# test1.net
KiCad netlist of a schematic drawn in EAGLE
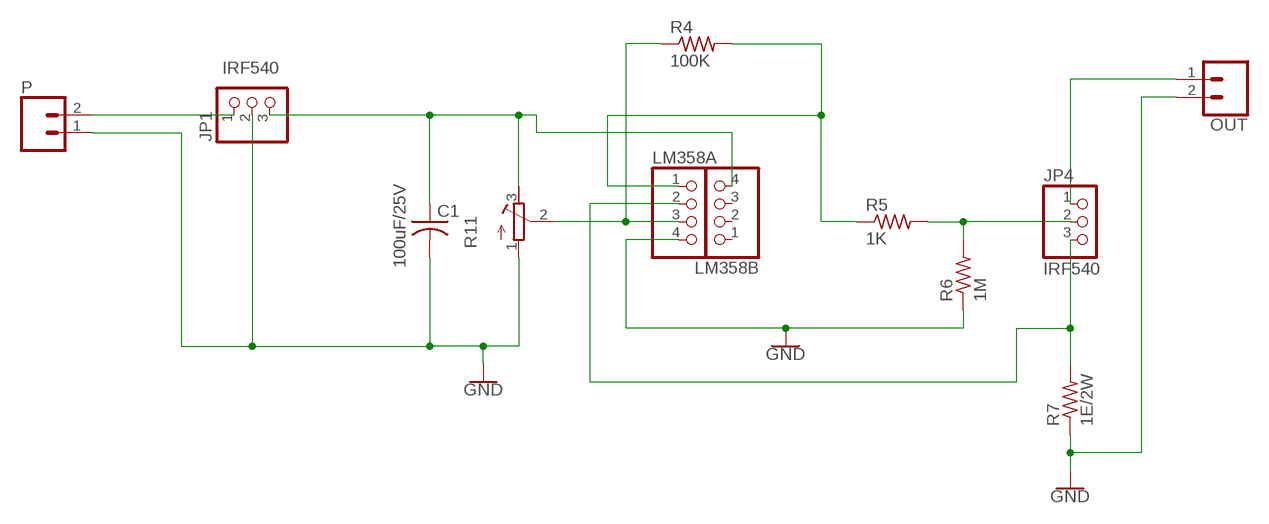
[diagram p0: schematic, sheet 1]

(export (version "E")
  (design (tool "Eeschema 10.0.6"))
  (components
    (comp (ref "C1")
      (value "100uF/25V")
      (footprint "eagle-import:C025-024X044")
      (libsource (lib "eagle-import") (part "C-US025-024X044"))
    )
    (comp (ref "JP1")
      (value "IRF540")
      (footprint "eagle-import:1X03")
      (libsource (lib "eagle-import") (part "PINHD-1X3"))
    )
    (comp (ref "JP4")
      (value "IRF540")
      (footprint "eagle-import:1X03")
      (libsource (lib "eagle-import") (part "PINHD-1X3"))
    )
    (comp (ref "LM358A")
      (value "PINHD-1X4")
      (footprint "eagle-import:1X04")
      (libsource (lib "eagle-import") (part "PINHD-1X4"))
    )
    (comp (ref "LM358B")
      (value "PINHD-1X4")
      (footprint "eagle-import:1X04")
      (libsource (lib "eagle-import") (part "PINHD-1X4"))
    )
    (comp (ref "OUT")
      (value "CONN_02")
      (footprint "eagle-import:1X02")
      (libsource (lib "eagle-import") (part "CONN_02"))
    )
    (comp (ref "P")
      (value "CONN_02")
      (footprint "eagle-import:1X02")
      (libsource (lib "eagle-import") (part "CONN_02"))
    )
    (comp (ref "R4")
      (value "100K")
      (footprint "eagle-import:0204_5")
      (libsource (lib "eagle-import") (part "R-US_0204/5"))
    )
    (comp (ref "R5")
      (value "1K")
      (footprint "eagle-import:0204_5")
      (libsource (lib "eagle-import") (part "R-US_0204/5"))
    )
    (comp (ref "R6")
      (value "1M")
      (footprint "eagle-import:0204_5")
      (libsource (lib "eagle-import") (part "R-US_0204/5"))
    )
    (comp (ref "R7")
      (value "1E/2W")
      (footprint "eagle-import:0204_5")
      (libsource (lib "eagle-import") (part "R-US_0204/5"))
    )
    (comp (ref "R11")
      (value "R-TRIMM3339P")
      (footprint "eagle-import:RTRIM3339P")
      (libsource (lib "eagle-import") (part "R-TRIMM3339P"))
    )
  )
  (nets
    (net (code "1") (name "GND") (class "Default")
      (node (ref "C1") (pin "2") (pinfunction "2_2") (pintype "passive"))
      (node (ref "JP1") (pin "2") (pinfunction "2_2") (pintype "passive"))
      (node (ref "LM358A") (pin "4") (pinfunction "4_4") (pintype "passive"))
      (node (ref "OUT") (pin "2") (pinfunction "2_2") (pintype "passive"))
      (node (ref "P") (pin "1") (pinfunction "1_1") (pintype "passive"))
      (node (ref "R11") (pin "1") (pinfunction "A_1") (pintype "passive"))
      (node (ref "R6") (pin "1") (pinfunction "1_1") (pintype "passive"))
      (node (ref "R7") (pin "1") (pinfunction "1_1") (pintype "passive"))
    )
    (net (code "2") (name "Net-(JP1-Pad1)") (class "Default")
      (node (ref "JP1") (pin "1") (pinfunction "1_1") (pintype "passive"))
      (node (ref "P") (pin "2") (pinfunction "2_2") (pintype "passive"))
    )
    (net (code "3") (name "Net-(JP4-Pad1)") (class "Default")
      (node (ref "JP4") (pin "1") (pinfunction "1_1") (pintype "passive"))
      (node (ref "OUT") (pin "1") (pinfunction "1_1") (pintype "passive"))
    )
    (net (code "4") (name "Net-(JP4-Pad2)") (class "Default")
      (node (ref "JP4") (pin "2") (pinfunction "2_2") (pintype "passive"))
      (node (ref "R5") (pin "2") (pinfunction "2_2") (pintype "passive"))
      (node (ref "R6") (pin "2") (pinfunction "2_2") (pintype "passive"))
    )
    (net (code "5") (name "Net-(JP4-Pad3)") (class "Default")
      (node (ref "JP4") (pin "3") (pinfunction "3_3") (pintype "passive"))
      (node (ref "LM358A") (pin "2") (pinfunction "2_2") (pintype "passive"))
      (node (ref "R7") (pin "2") (pinfunction "2_2") (pintype "passive"))
    )
    (net (code "6") (name "Net-(LM358A-Pad1)") (class "Default")
      (node (ref "LM358A") (pin "1") (pinfunction "1_1") (pintype "passive"))
      (node (ref "R4") (pin "2") (pinfunction "2_2") (pintype "passive"))
      (node (ref "R5") (pin "1") (pinfunction "1_1") (pintype "passive"))
    )
    (net (code "7") (name "Net-(R11-E)") (class "Default")
      (node (ref "C1") (pin "1") (pinfunction "1_1") (pintype "passive"))
      (node (ref "JP1") (pin "3") (pinfunction "3_3") (pintype "passive"))
      (node (ref "LM358B") (pin "4") (pinfunction "4_4") (pintype "passive"))
      (node (ref "R11") (pin "3") (pinfunction "E_3") (pintype "passive"))
    )
    (net (code "8") (name "Net-(R11-S)") (class "Default")
      (node (ref "LM358A") (pin "3") (pinfunction "3_3") (pintype "passive"))
      (node (ref "R11") (pin "2") (pinfunction "S_2") (pintype "passive"))
      (node (ref "R4") (pin "1") (pinfunction "1_1") (pintype "passive"))
    )
    (net (code "9") (name "unconnected-(LM358B-Pad1)") (class "Default")
      (node (ref "LM358B") (pin "1") (pinfunction "1_1") (pintype "passive"))
    )
    (net (code "10") (name "unconnected-(LM358B-Pad2)") (class "Default")
      (node (ref "LM358B") (pin "2") (pinfunction "2_2") (pintype "passive"))
    )
    (net (code "11") (name "unconnected-(LM358B-Pad3)") (class "Default")
      (node (ref "LM358B") (pin "3") (pinfunction "3_3") (pintype "passive"))
    )
  )
)
